# 00.net
KiCad netlist of a schematic drawn in EAGLE
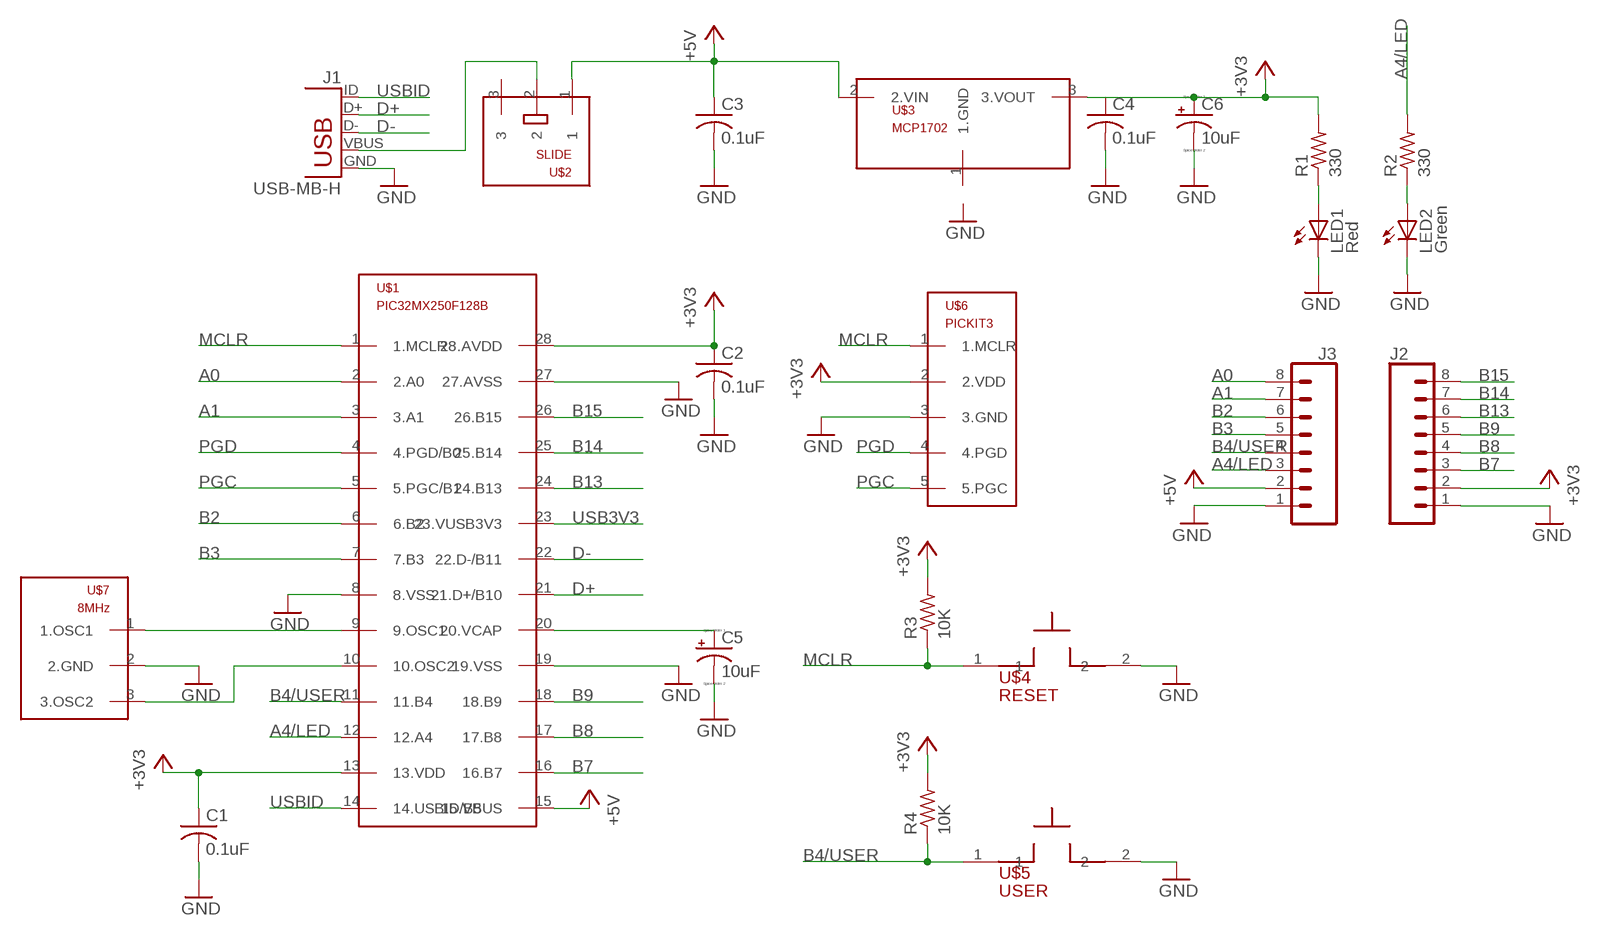
[diagram p0: schematic, sheet 1]

(export (version "E")
  (design (tool "Eeschema 10.0.6"))
  (components
    (comp (ref "C1")
      (value "0.1uF")
      (footprint "eagle-import:C025-025X050")
      (libsource (lib "eagle-import") (part "C-US025-025X050"))
    )
    (comp (ref "C2")
      (value "0.1uF")
      (footprint "eagle-import:C025-025X050")
      (libsource (lib "eagle-import") (part "C-US025-025X050"))
    )
    (comp (ref "C3")
      (value "0.1uF")
      (footprint "eagle-import:C025-025X050")
      (libsource (lib "eagle-import") (part "C-US025-025X050"))
    )
    (comp (ref "C4")
      (value "0.1uF")
      (footprint "eagle-import:C025-025X050")
      (libsource (lib "eagle-import") (part "C-US025-025X050"))
    )
    (comp (ref "C5")
      (value "10uF")
      (footprint "eagle-import:B45181B")
      (libsource (lib "eagle-import") (part "CPOL-USB45181B"))
    )
    (comp (ref "C6")
      (value "10uF")
      (footprint "eagle-import:B45181B")
      (libsource (lib "eagle-import") (part "CPOL-USB45181B"))
    )
    (comp (ref "J1")
      (value "USB-MB-H")
      (footprint "eagle-import:USB-MB-H")
      (libsource (lib "eagle-import") (part "USB-MB-H"))
    )
    (comp (ref "J2")
      (value "CONN_08\"")
      (footprint "eagle-import:1X08")
      (libsource (lib "eagle-import") (part "CONN_08{dblquote}"))
    )
    (comp (ref "J3")
      (value "CONN_08\"")
      (footprint "eagle-import:1X08")
      (libsource (lib "eagle-import") (part "CONN_08{dblquote}"))
    )
    (comp (ref "LED1")
      (value "Red")
      (footprint "eagle-import:LED3MM")
      (libsource (lib "eagle-import") (part "LED3MM"))
    )
    (comp (ref "LED2")
      (value "Green")
      (footprint "eagle-import:LED3MM")
      (libsource (lib "eagle-import") (part "LED3MM"))
    )
    (comp (ref "R1")
      (value "330")
      (footprint "eagle-import:0207_10")
      (libsource (lib "eagle-import") (part "R-US_0207/10"))
    )
    (comp (ref "R2")
      (value "330")
      (footprint "eagle-import:0207_10")
      (libsource (lib "eagle-import") (part "R-US_0207/10"))
    )
    (comp (ref "R3")
      (value "10K")
      (footprint "eagle-import:0207_10")
      (libsource (lib "eagle-import") (part "R-US_0207/10"))
    )
    (comp (ref "R4")
      (value "10K")
      (footprint "eagle-import:0207_10")
      (libsource (lib "eagle-import") (part "R-US_0207/10"))
    )
    (comp (ref "U$1")
      (value "PIC32MX250F128B")
      (footprint "eagle-import:DIL28-3")
      (libsource (lib "eagle-import") (part "PIC32MX250F128B"))
    )
    (comp (ref "U$2")
      (value "SLIDE")
      (footprint "eagle-import:SLIDE")
      (libsource (lib "eagle-import") (part "SLIDE"))
    )
    (comp (ref "U$3")
      (value "MCP1702")
      (footprint "eagle-import:TO92")
      (libsource (lib "eagle-import") (part "MCP1702"))
    )
    (comp (ref "U$4")
      (value "RESET")
      (footprint "eagle-import:PB")
      (libsource (lib "eagle-import") (part "PB"))
    )
    (comp (ref "U$5")
      (value "USER")
      (footprint "eagle-import:PB")
      (libsource (lib "eagle-import") (part "PB"))
    )
    (comp (ref "U$6")
      (value "PICKIT3")
      (footprint "eagle-import:1X05")
      (libsource (lib "eagle-import") (part "PICKIT3"))
    )
    (comp (ref "U$7")
      (value "8MHz")
      (footprint "eagle-import:OSC")
      (libsource (lib "eagle-import") (part "OSC"))
    )
  )
  (nets
    (net (code "1") (name "+3V3") (class "Default")
      (node (ref "C1") (pin "1") (pinfunction "1_1") (pintype "passive"))
      (node (ref "C2") (pin "1") (pinfunction "1_1") (pintype "passive"))
      (node (ref "C6") (pin "+") (pinfunction "+_+") (pintype "passive"))
      (node (ref "J2") (pin "2") (pinfunction "2_2") (pintype "passive"))
      (node (ref "R1") (pin "2") (pinfunction "2_2") (pintype "passive"))
      (node (ref "R3") (pin "2") (pinfunction "2_2") (pintype "passive"))
      (node (ref "R4") (pin "2") (pinfunction "2_2") (pintype "passive"))
      (node (ref "U$1") (pin "13") (pinfunction "13.VDD_13") (pintype "bidirectional"))
      (node (ref "U$1") (pin "28") (pinfunction "28.AVDD_28") (pintype "bidirectional"))
      (node (ref "U$3") (pin "3") (pinfunction "3.VOUT_3") (pintype "bidirectional"))
      (node (ref "U$6") (pin "2") (pinfunction "2.VDD_2") (pintype "bidirectional"))
    )
    (net (code "2") (name "+5V") (class "Default")
      (node (ref "C3") (pin "1") (pinfunction "1_1") (pintype "passive"))
      (node (ref "J3") (pin "2") (pinfunction "2_2") (pintype "passive"))
      (node (ref "U$1") (pin "15") (pinfunction "15.VBUS_15") (pintype "bidirectional"))
      (node (ref "U$2") (pin "1") (pinfunction "1_1") (pintype "bidirectional"))
      (node (ref "U$3") (pin "2") (pinfunction "2.VIN_2") (pintype "bidirectional"))
    )
    (net (code "3") (name "/A0") (class "Default")
      (node (ref "J3") (pin "8") (pinfunction "8_8") (pintype "passive"))
      (node (ref "U$1") (pin "2") (pinfunction "2.A0_2") (pintype "bidirectional"))
    )
    (net (code "4") (name "/A1") (class "Default")
      (node (ref "J3") (pin "7") (pinfunction "7_7") (pintype "passive"))
      (node (ref "U$1") (pin "3") (pinfunction "3.A1_3") (pintype "bidirectional"))
    )
    (net (code "5") (name "/A4{slash}LED") (class "Default")
      (node (ref "J3") (pin "3") (pinfunction "3_3") (pintype "passive"))
      (node (ref "R2") (pin "2") (pinfunction "2_2") (pintype "passive"))
      (node (ref "U$1") (pin "12") (pinfunction "12.A4_12") (pintype "bidirectional"))
    )
    (net (code "6") (name "/B2") (class "Default")
      (node (ref "J3") (pin "6") (pinfunction "6_6") (pintype "passive"))
      (node (ref "U$1") (pin "6") (pinfunction "6.B2_6") (pintype "bidirectional"))
    )
    (net (code "7") (name "/B3") (class "Default")
      (node (ref "J3") (pin "5") (pinfunction "5_5") (pintype "passive"))
      (node (ref "U$1") (pin "7") (pinfunction "7.B3_7") (pintype "bidirectional"))
    )
    (net (code "8") (name "/B4{slash}USER") (class "Default")
      (node (ref "J3") (pin "4") (pinfunction "4_4") (pintype "passive"))
      (node (ref "R4") (pin "1") (pinfunction "1_1") (pintype "passive"))
      (node (ref "U$1") (pin "11") (pinfunction "11.B4_11") (pintype "bidirectional"))
      (node (ref "U$5") (pin "1") (pinfunction "1_1") (pintype "bidirectional"))
    )
    (net (code "9") (name "/B7") (class "Default")
      (node (ref "J2") (pin "3") (pinfunction "3_3") (pintype "passive"))
      (node (ref "U$1") (pin "16") (pinfunction "16.B7_16") (pintype "bidirectional"))
    )
    (net (code "10") (name "/B8") (class "Default")
      (node (ref "J2") (pin "4") (pinfunction "4_4") (pintype "passive"))
      (node (ref "U$1") (pin "17") (pinfunction "17.B8_17") (pintype "bidirectional"))
    )
    (net (code "11") (name "/B9") (class "Default")
      (node (ref "J2") (pin "5") (pinfunction "5_5") (pintype "passive"))
      (node (ref "U$1") (pin "18") (pinfunction "18.B9_18") (pintype "bidirectional"))
    )
    (net (code "12") (name "/B13") (class "Default")
      (node (ref "J2") (pin "6") (pinfunction "6_6") (pintype "passive"))
      (node (ref "U$1") (pin "24") (pinfunction "24.B13_24") (pintype "bidirectional"))
    )
    (net (code "13") (name "/B14") (class "Default")
      (node (ref "J2") (pin "7") (pinfunction "7_7") (pintype "passive"))
      (node (ref "U$1") (pin "25") (pinfunction "25.B14_25") (pintype "bidirectional"))
    )
    (net (code "14") (name "/B15") (class "Default")
      (node (ref "J2") (pin "8") (pinfunction "8_8") (pintype "passive"))
      (node (ref "U$1") (pin "26") (pinfunction "26.B15_26") (pintype "bidirectional"))
    )
    (net (code "15") (name "/D+") (class "Default")
      (node (ref "J1") (pin "D+") (pinfunction "D+_D+") (pintype "bidirectional"))
      (node (ref "U$1") (pin "21") (pinfunction "21.D+/B10_21") (pintype "bidirectional"))
    )
    (net (code "16") (name "/D-") (class "Default")
      (node (ref "J1") (pin "D-") (pinfunction "D-_D-") (pintype "bidirectional"))
      (node (ref "U$1") (pin "22") (pinfunction "22.D-/B11_22") (pintype "bidirectional"))
    )
    (net (code "17") (name "/MCLR") (class "Default")
      (node (ref "R3") (pin "1") (pinfunction "1_1") (pintype "passive"))
      (node (ref "U$1") (pin "1") (pinfunction "1.MCLR_1") (pintype "bidirectional"))
      (node (ref "U$4") (pin "1") (pinfunction "1_1") (pintype "bidirectional"))
      (node (ref "U$6") (pin "1") (pinfunction "1.MCLR_1") (pintype "bidirectional"))
    )
    (net (code "18") (name "/PGC") (class "Default")
      (node (ref "U$1") (pin "5") (pinfunction "5.PGC/B1_5") (pintype "bidirectional"))
      (node (ref "U$6") (pin "5") (pinfunction "5.PGC_5") (pintype "bidirectional"))
    )
    (net (code "19") (name "/PGD") (class "Default")
      (node (ref "U$1") (pin "4") (pinfunction "4.PGD/B0_4") (pintype "bidirectional"))
      (node (ref "U$6") (pin "4") (pinfunction "4.PGD_4") (pintype "bidirectional"))
    )
    (net (code "20") (name "/USB3V3") (class "Default")
      (node (ref "U$1") (pin "23") (pinfunction "23.VUSB3V3_23") (pintype "bidirectional"))
    )
    (net (code "21") (name "/USBID") (class "Default")
      (node (ref "J1") (pin "ID") (pinfunction "ID_ID") (pintype "bidirectional"))
      (node (ref "U$1") (pin "14") (pinfunction "14.USBID/B5_14") (pintype "bidirectional"))
    )
    (net (code "22") (name "GND") (class "Default")
      (node (ref "C1") (pin "2") (pinfunction "2_2") (pintype "passive"))
      (node (ref "C2") (pin "2") (pinfunction "2_2") (pintype "passive"))
      (node (ref "C3") (pin "2") (pinfunction "2_2") (pintype "passive"))
      (node (ref "C4") (pin "2") (pinfunction "2_2") (pintype "passive"))
      (node (ref "C5") (pin "-") (pinfunction "-_-") (pintype "passive"))
      (node (ref "C6") (pin "-") (pinfunction "-_-") (pintype "passive"))
      (node (ref "J1") (pin "GND") (pinfunction "GND_GND") (pintype "bidirectional"))
      (node (ref "J2") (pin "1") (pinfunction "1_1") (pintype "passive"))
      (node (ref "J3") (pin "1") (pinfunction "1_1") (pintype "passive"))
      (node (ref "LED1") (pin "K") (pinfunction "C_K") (pintype "passive"))
      (node (ref "LED2") (pin "K") (pinfunction "C_K") (pintype "passive"))
      (node (ref "U$1") (pin "19") (pinfunction "19.VSS_19") (pintype "bidirectional"))
      (node (ref "U$1") (pin "27") (pinfunction "27.AVSS_27") (pintype "bidirectional"))
      (node (ref "U$1") (pin "8") (pinfunction "8.VSS_8") (pintype "bidirectional"))
      (node (ref "U$4") (pin "2") (pinfunction "2_2") (pintype "bidirectional"))
      (node (ref "U$5") (pin "2") (pinfunction "2_2") (pintype "bidirectional"))
      (node (ref "U$6") (pin "3") (pinfunction "3.GND_3") (pintype "bidirectional"))
      (node (ref "U$7") (pin "2") (pinfunction "2.GND_2") (pintype "bidirectional"))
    )
    (net (code "23") (name "Net-(J1-PadVBUS)") (class "Default")
      (node (ref "J1") (pin "VBUS") (pinfunction "VBUS_VBUS") (pintype "bidirectional"))
      (node (ref "U$2") (pin "2") (pinfunction "2_2") (pintype "bidirectional"))
    )
    (net (code "24") (name "Net-(LED1-PadA)") (class "Default")
      (node (ref "LED1") (pin "A") (pinfunction "A_A") (pintype "passive"))
      (node (ref "R1") (pin "1") (pinfunction "1_1") (pintype "passive"))
    )
    (net (code "25") (name "Net-(LED2-PadA)") (class "Default")
      (node (ref "LED2") (pin "A") (pinfunction "A_A") (pintype "passive"))
      (node (ref "R2") (pin "1") (pinfunction "1_1") (pintype "passive"))
    )
    (net (code "26") (name "Net-(U$1-9.OSC1)") (class "Default")
      (node (ref "U$1") (pin "9") (pinfunction "9.OSC1_9") (pintype "bidirectional"))
      (node (ref "U$7") (pin "1") (pinfunction "1.OSC1_1") (pintype "bidirectional"))
    )
    (net (code "27") (name "Net-(U$1-10.OSC2)") (class "Default")
      (node (ref "U$1") (pin "10") (pinfunction "10.OSC2_10") (pintype "bidirectional"))
      (node (ref "U$7") (pin "3") (pinfunction "3.OSC2_3") (pintype "bidirectional"))
    )
    (net (code "28") (name "Net-(U$1-20.VCAP)") (class "Default")
      (node (ref "C5") (pin "+") (pinfunction "+_+") (pintype "passive"))
      (node (ref "U$1") (pin "20") (pinfunction "20.VCAP_20") (pintype "bidirectional"))
    )
    (net (code "29") (name "unconnected-(C4-Pad1)") (class "Default")
      (node (ref "C4") (pin "1") (pinfunction "1_1") (pintype "passive"))
    )
    (net (code "30") (name "unconnected-(U$2-Pad3)") (class "Default")
      (node (ref "U$2") (pin "3") (pinfunction "3_3") (pintype "bidirectional"))
    )
    (net (code "31") (name "unconnected-(U$3-1.GND-Pad1)") (class "Default")
      (node (ref "U$3") (pin "1") (pinfunction "1.GND_1") (pintype "bidirectional"))
    )
  )
)
